# main.net
KiCad netlist of a schematic drawn in EAGLE
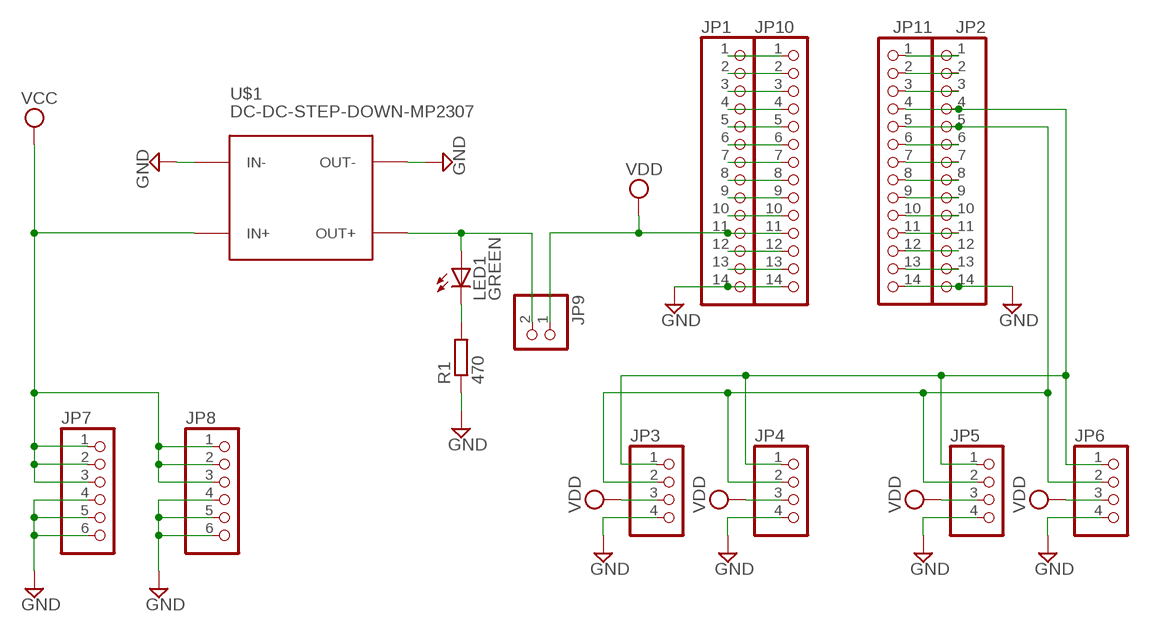
[diagram p0: schematic, sheet 1]

(export (version "E")
  (design (tool "Eeschema 10.0.6"))
  (components
    (comp (ref "JP1")
      (value "PINHD-1X14_2.54")
      (footprint "eagle-import:1X14")
      (libsource (lib "eagle-import") (part "PINHD-1X14_2.54"))
    )
    (comp (ref "JP2")
      (value "PINHD-1X14_2.54")
      (footprint "eagle-import:1X14")
      (libsource (lib "eagle-import") (part "PINHD-1X14_2.54"))
    )
    (comp (ref "JP3")
      (value "PINHD-1X4_2.54-90°")
      (footprint "eagle-import:1X04_90")
      (libsource (lib "eagle-import") (part "PINHD-1X4_2.54-90°"))
    )
    (comp (ref "JP4")
      (value "PINHD-1X4_2.54-90°")
      (footprint "eagle-import:1X04_90")
      (libsource (lib "eagle-import") (part "PINHD-1X4_2.54-90°"))
    )
    (comp (ref "JP5")
      (value "PINHD-1X4_2.54")
      (footprint "eagle-import:1X04")
      (libsource (lib "eagle-import") (part "PINHD-1X4_2.54"))
    )
    (comp (ref "JP6")
      (value "PINHD-1X4_2.54")
      (footprint "eagle-import:1X04")
      (libsource (lib "eagle-import") (part "PINHD-1X4_2.54"))
    )
    (comp (ref "JP7")
      (value "PINHD-1X6_2.54-90°")
      (footprint "eagle-import:1X06_90")
      (libsource (lib "eagle-import") (part "PINHD-1X6_2.54-90°"))
    )
    (comp (ref "JP8")
      (value "PINHD-1X6_2.54-90°")
      (footprint "eagle-import:1X06_90")
      (libsource (lib "eagle-import") (part "PINHD-1X6_2.54-90°"))
    )
    (comp (ref "JP9")
      (value "PINHD-1X2_2.54")
      (footprint "eagle-import:1X02")
      (libsource (lib "eagle-import") (part "PINHD-1X2_2.54"))
    )
    (comp (ref "JP10")
      (value "PINHD-1X14_2.54")
      (footprint "eagle-import:1X14")
      (libsource (lib "eagle-import") (part "PINHD-1X14_2.54"))
    )
    (comp (ref "JP11")
      (value "PINHD-1X14_2.54")
      (footprint "eagle-import:1X14")
      (libsource (lib "eagle-import") (part "PINHD-1X14_2.54"))
    )
    (comp (ref "LED1")
      (value "GREEN")
      (footprint "eagle-import:CHIP-LED0805")
      (libsource (lib "eagle-import") (part "LEDCHIP-LED0805"))
    )
    (comp (ref "R1")
      (value "470")
      (footprint "eagle-import:R0805")
      (libsource (lib "eagle-import") (part "R-EU_R0805"))
    )
    (comp (ref "U$1")
      (value "DC-DC-STEP-DOWN-MP2307")
      (footprint "eagle-import:DC-DC-STEP-DOWN-MP2307")
      (libsource (lib "eagle-import") (part "DC-DC-STEP-DOWN-MP2307"))
    )
  )
  (nets
    (net (code "1") (name "GND") (class "Default")
      (node (ref "JP1") (pin "14") (pinfunction "14_14") (pintype "passive"))
      (node (ref "JP10") (pin "14") (pinfunction "14_14") (pintype "passive"))
      (node (ref "JP11") (pin "14") (pinfunction "14_14") (pintype "passive"))
      (node (ref "JP2") (pin "14") (pinfunction "14_14") (pintype "passive"))
      (node (ref "JP3") (pin "4") (pinfunction "4_4") (pintype "passive"))
      (node (ref "JP4") (pin "4") (pinfunction "4_4") (pintype "passive"))
      (node (ref "JP5") (pin "4") (pinfunction "4_4") (pintype "passive"))
      (node (ref "JP6") (pin "4") (pinfunction "4_4") (pintype "passive"))
      (node (ref "JP7") (pin "4") (pinfunction "4_4") (pintype "passive"))
      (node (ref "JP7") (pin "5") (pinfunction "5_5") (pintype "passive"))
      (node (ref "JP7") (pin "6") (pinfunction "6_6") (pintype "passive"))
      (node (ref "JP8") (pin "4") (pinfunction "4_4") (pintype "passive"))
      (node (ref "JP8") (pin "5") (pinfunction "5_5") (pintype "passive"))
      (node (ref "JP8") (pin "6") (pinfunction "6_6") (pintype "passive"))
      (node (ref "R1") (pin "1") (pinfunction "1_1") (pintype "passive"))
      (node (ref "U$1") (pin "IN-") (pinfunction "IN-_IN-") (pintype "bidirectional"))
      (node (ref "U$1") (pin "OUT-") (pinfunction "OUT-_OUT-") (pintype "bidirectional"))
    )
    (net (code "2") (name "Net-(JP1-Pad1)") (class "Default")
      (node (ref "JP1") (pin "1") (pinfunction "1_1") (pintype "passive"))
      (node (ref "JP10") (pin "1") (pinfunction "1_1") (pintype "passive"))
    )
    (net (code "3") (name "Net-(JP1-Pad2)") (class "Default")
      (node (ref "JP1") (pin "2") (pinfunction "2_2") (pintype "passive"))
      (node (ref "JP10") (pin "2") (pinfunction "2_2") (pintype "passive"))
    )
    (net (code "4") (name "Net-(JP1-Pad3)") (class "Default")
      (node (ref "JP1") (pin "3") (pinfunction "3_3") (pintype "passive"))
      (node (ref "JP10") (pin "3") (pinfunction "3_3") (pintype "passive"))
    )
    (net (code "5") (name "Net-(JP1-Pad4)") (class "Default")
      (node (ref "JP1") (pin "4") (pinfunction "4_4") (pintype "passive"))
      (node (ref "JP10") (pin "4") (pinfunction "4_4") (pintype "passive"))
    )
    (net (code "6") (name "Net-(JP1-Pad5)") (class "Default")
      (node (ref "JP1") (pin "5") (pinfunction "5_5") (pintype "passive"))
      (node (ref "JP10") (pin "5") (pinfunction "5_5") (pintype "passive"))
    )
    (net (code "7") (name "Net-(JP1-Pad6)") (class "Default")
      (node (ref "JP1") (pin "6") (pinfunction "6_6") (pintype "passive"))
      (node (ref "JP10") (pin "6") (pinfunction "6_6") (pintype "passive"))
    )
    (net (code "8") (name "Net-(JP1-Pad7)") (class "Default")
      (node (ref "JP1") (pin "7") (pinfunction "7_7") (pintype "passive"))
      (node (ref "JP10") (pin "7") (pinfunction "7_7") (pintype "passive"))
    )
    (net (code "9") (name "Net-(JP1-Pad8)") (class "Default")
      (node (ref "JP1") (pin "8") (pinfunction "8_8") (pintype "passive"))
      (node (ref "JP10") (pin "8") (pinfunction "8_8") (pintype "passive"))
    )
    (net (code "10") (name "Net-(JP1-Pad9)") (class "Default")
      (node (ref "JP1") (pin "9") (pinfunction "9_9") (pintype "passive"))
      (node (ref "JP10") (pin "9") (pinfunction "9_9") (pintype "passive"))
    )
    (net (code "11") (name "Net-(JP1-Pad10)") (class "Default")
      (node (ref "JP1") (pin "10") (pinfunction "10_10") (pintype "passive"))
      (node (ref "JP10") (pin "10") (pinfunction "10_10") (pintype "passive"))
    )
    (net (code "12") (name "Net-(JP1-Pad12)") (class "Default")
      (node (ref "JP1") (pin "12") (pinfunction "12_12") (pintype "passive"))
      (node (ref "JP10") (pin "12") (pinfunction "12_12") (pintype "passive"))
    )
    (net (code "13") (name "Net-(JP1-Pad13)") (class "Default")
      (node (ref "JP1") (pin "13") (pinfunction "13_13") (pintype "passive"))
      (node (ref "JP10") (pin "13") (pinfunction "13_13") (pintype "passive"))
    )
    (net (code "14") (name "Net-(JP9-Pad2)") (class "Default")
      (node (ref "JP9") (pin "2") (pinfunction "2_2") (pintype "passive"))
      (node (ref "LED1") (pin "A") (pinfunction "A_A") (pintype "passive"))
      (node (ref "U$1") (pin "OUT+") (pinfunction "OUT+_OUT+") (pintype "bidirectional"))
    )
    (net (code "15") (name "Net-(JP11-Pad1)") (class "Default")
      (node (ref "JP11") (pin "1") (pinfunction "1_1") (pintype "passive"))
      (node (ref "JP2") (pin "1") (pinfunction "1_1") (pintype "passive"))
    )
    (net (code "16") (name "Net-(JP11-Pad2)") (class "Default")
      (node (ref "JP11") (pin "2") (pinfunction "2_2") (pintype "passive"))
      (node (ref "JP2") (pin "2") (pinfunction "2_2") (pintype "passive"))
    )
    (net (code "17") (name "Net-(JP11-Pad3)") (class "Default")
      (node (ref "JP11") (pin "3") (pinfunction "3_3") (pintype "passive"))
      (node (ref "JP2") (pin "3") (pinfunction "3_3") (pintype "passive"))
    )
    (net (code "18") (name "Net-(JP11-Pad4)") (class "Default")
      (node (ref "JP11") (pin "4") (pinfunction "4_4") (pintype "passive"))
      (node (ref "JP2") (pin "4") (pinfunction "4_4") (pintype "passive"))
      (node (ref "JP3") (pin "1") (pinfunction "1_1") (pintype "passive"))
      (node (ref "JP4") (pin "1") (pinfunction "1_1") (pintype "passive"))
      (node (ref "JP5") (pin "1") (pinfunction "1_1") (pintype "passive"))
      (node (ref "JP6") (pin "1") (pinfunction "1_1") (pintype "passive"))
    )
    (net (code "19") (name "Net-(JP11-Pad5)") (class "Default")
      (node (ref "JP11") (pin "5") (pinfunction "5_5") (pintype "passive"))
      (node (ref "JP2") (pin "5") (pinfunction "5_5") (pintype "passive"))
      (node (ref "JP3") (pin "2") (pinfunction "2_2") (pintype "passive"))
      (node (ref "JP4") (pin "2") (pinfunction "2_2") (pintype "passive"))
      (node (ref "JP5") (pin "2") (pinfunction "2_2") (pintype "passive"))
      (node (ref "JP6") (pin "2") (pinfunction "2_2") (pintype "passive"))
    )
    (net (code "20") (name "Net-(JP11-Pad6)") (class "Default")
      (node (ref "JP11") (pin "6") (pinfunction "6_6") (pintype "passive"))
      (node (ref "JP2") (pin "6") (pinfunction "6_6") (pintype "passive"))
    )
    (net (code "21") (name "Net-(JP11-Pad7)") (class "Default")
      (node (ref "JP11") (pin "7") (pinfunction "7_7") (pintype "passive"))
      (node (ref "JP2") (pin "7") (pinfunction "7_7") (pintype "passive"))
    )
    (net (code "22") (name "Net-(JP11-Pad8)") (class "Default")
      (node (ref "JP11") (pin "8") (pinfunction "8_8") (pintype "passive"))
      (node (ref "JP2") (pin "8") (pinfunction "8_8") (pintype "passive"))
    )
    (net (code "23") (name "Net-(JP11-Pad9)") (class "Default")
      (node (ref "JP11") (pin "9") (pinfunction "9_9") (pintype "passive"))
      (node (ref "JP2") (pin "9") (pinfunction "9_9") (pintype "passive"))
    )
    (net (code "24") (name "Net-(JP11-Pad10)") (class "Default")
      (node (ref "JP11") (pin "10") (pinfunction "10_10") (pintype "passive"))
      (node (ref "JP2") (pin "10") (pinfunction "10_10") (pintype "passive"))
    )
    (net (code "25") (name "Net-(JP11-Pad11)") (class "Default")
      (node (ref "JP11") (pin "11") (pinfunction "11_11") (pintype "passive"))
      (node (ref "JP2") (pin "11") (pinfunction "11_11") (pintype "passive"))
    )
    (net (code "26") (name "Net-(JP11-Pad12)") (class "Default")
      (node (ref "JP11") (pin "12") (pinfunction "12_12") (pintype "passive"))
      (node (ref "JP2") (pin "12") (pinfunction "12_12") (pintype "passive"))
    )
    (net (code "27") (name "Net-(JP11-Pad13)") (class "Default")
      (node (ref "JP11") (pin "13") (pinfunction "13_13") (pintype "passive"))
      (node (ref "JP2") (pin "13") (pinfunction "13_13") (pintype "passive"))
    )
    (net (code "28") (name "Net-(LED1-PadC)") (class "Default")
      (node (ref "LED1") (pin "C") (pinfunction "C_C") (pintype "passive"))
      (node (ref "R1") (pin "2") (pinfunction "2_2") (pintype "passive"))
    )
    (net (code "29") (name "VCC") (class "Default")
      (node (ref "JP7") (pin "1") (pinfunction "1_1") (pintype "passive"))
      (node (ref "JP7") (pin "2") (pinfunction "2_2") (pintype "passive"))
      (node (ref "JP7") (pin "3") (pinfunction "3_3") (pintype "passive"))
      (node (ref "JP8") (pin "1") (pinfunction "1_1") (pintype "passive"))
      (node (ref "JP8") (pin "2") (pinfunction "2_2") (pintype "passive"))
      (node (ref "JP8") (pin "3") (pinfunction "3_3") (pintype "passive"))
      (node (ref "U$1") (pin "IN+") (pinfunction "IN+_IN+") (pintype "bidirectional"))
    )
    (net (code "30") (name "VDD") (class "Default")
      (node (ref "JP1") (pin "11") (pinfunction "11_11") (pintype "passive"))
      (node (ref "JP10") (pin "11") (pinfunction "11_11") (pintype "passive"))
      (node (ref "JP3") (pin "3") (pinfunction "3_3") (pintype "passive"))
      (node (ref "JP4") (pin "3") (pinfunction "3_3") (pintype "passive"))
      (node (ref "JP5") (pin "3") (pinfunction "3_3") (pintype "passive"))
      (node (ref "JP6") (pin "3") (pinfunction "3_3") (pintype "passive"))
      (node (ref "JP9") (pin "1") (pinfunction "1_1") (pintype "passive"))
    )
  )
)
